# nrf52_pcb_layout.net
KiCad netlist of a schematic drawn in EAGLE
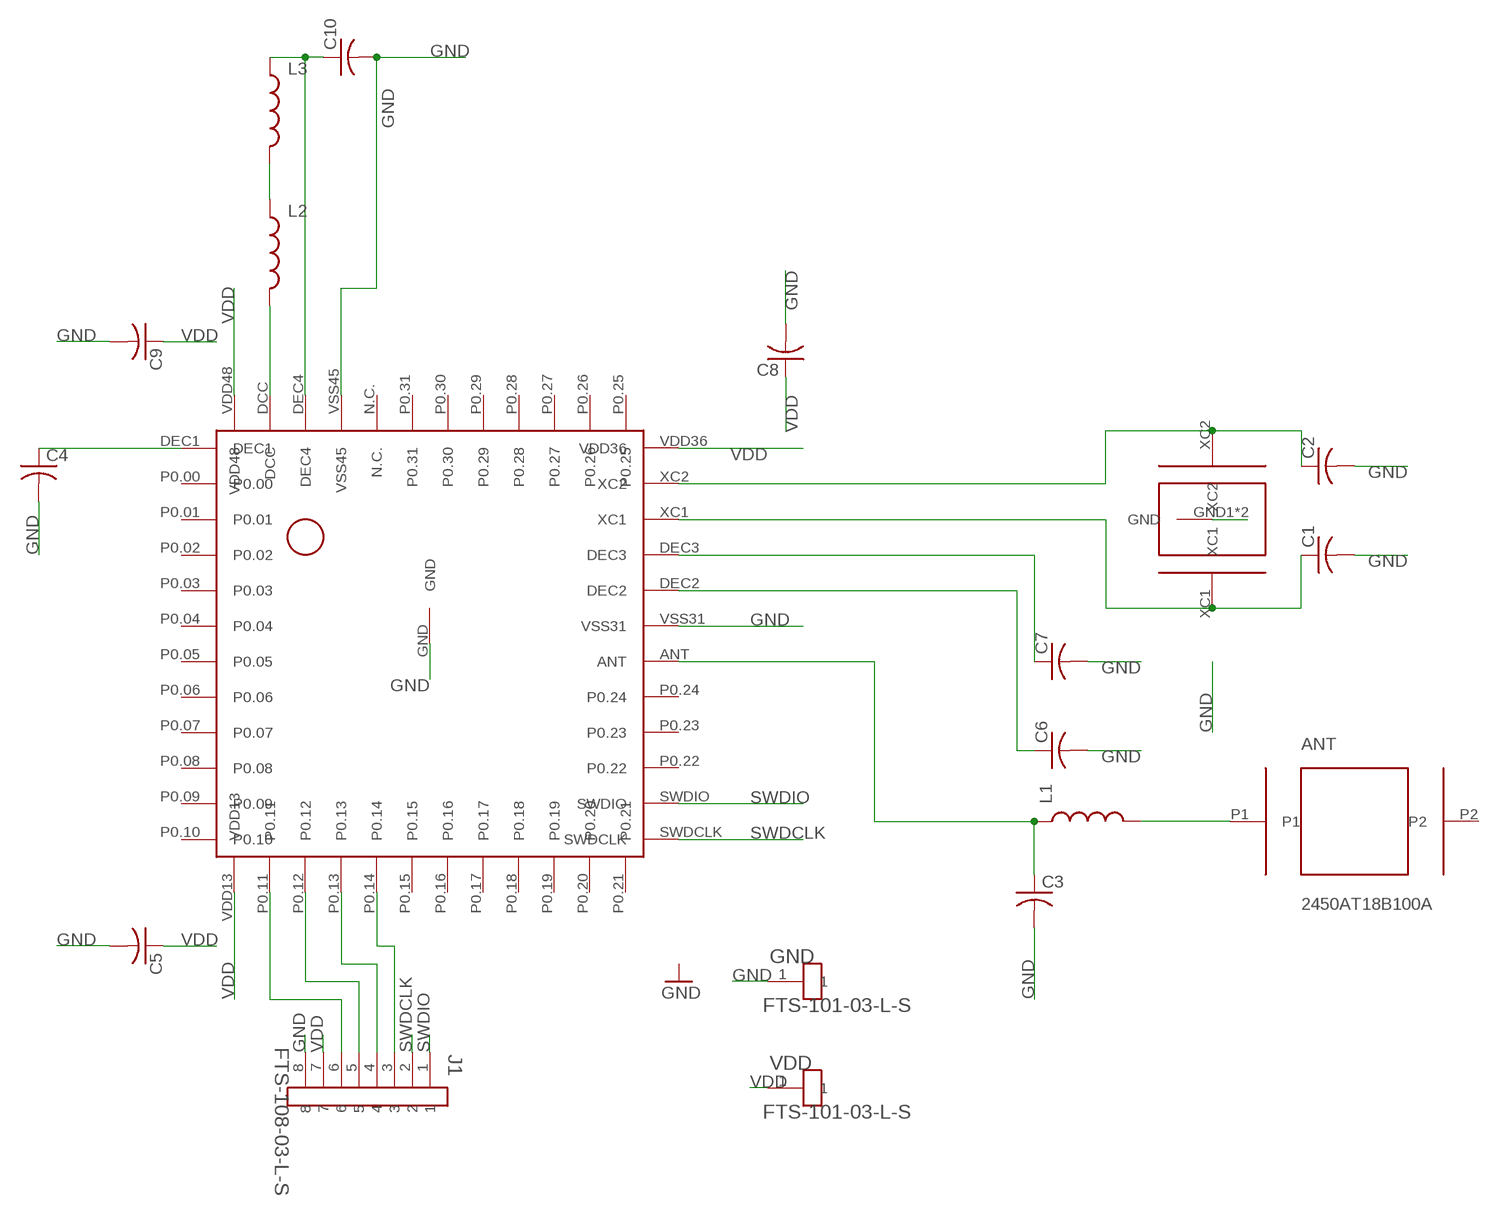
[diagram p0: schematic, sheet 1]

(export (version "E")
  (design (tool "Eeschema 10.0.6"))
  (components
    (comp (ref "ANT")
      (value "2450AT18B100A")
      (footprint "eagle-import:2450AT18B100")
      (libsource (lib "eagle-import") (part "2450AT18B100A"))
    )
    (comp (ref "C1")
      (value "C-USC0402")
      (footprint "eagle-import:C0402")
      (libsource (lib "eagle-import") (part "C-USC0402"))
    )
    (comp (ref "C2")
      (value "C-USC0402")
      (footprint "eagle-import:C0402")
      (libsource (lib "eagle-import") (part "C-USC0402"))
    )
    (comp (ref "C3")
      (value "C-USC0402")
      (footprint "eagle-import:C0402")
      (libsource (lib "eagle-import") (part "C-USC0402"))
    )
    (comp (ref "C4")
      (value "C-USC0402")
      (footprint "eagle-import:C0402")
      (libsource (lib "eagle-import") (part "C-USC0402"))
    )
    (comp (ref "C5")
      (value "C-USC0402")
      (footprint "eagle-import:C0402")
      (libsource (lib "eagle-import") (part "C-USC0402"))
    )
    (comp (ref "C6")
      (value "C-USC0402")
      (footprint "eagle-import:C0402")
      (libsource (lib "eagle-import") (part "C-USC0402"))
    )
    (comp (ref "C7")
      (value "C-USC0402")
      (footprint "eagle-import:C0402")
      (libsource (lib "eagle-import") (part "C-USC0402"))
    )
    (comp (ref "C8")
      (value "C-USC0402")
      (footprint "eagle-import:C0402")
      (libsource (lib "eagle-import") (part "C-USC0402"))
    )
    (comp (ref "C9")
      (value "C-USC0603")
      (footprint "eagle-import:C0603")
      (libsource (lib "eagle-import") (part "C-USC0603"))
    )
    (comp (ref "C10")
      (value "C-USC0603")
      (footprint "eagle-import:C0603")
      (libsource (lib "eagle-import") (part "C-USC0603"))
    )
    (comp (ref "GND")
      (value "FTS-101-03-L-S")
      (footprint "eagle-import:SAMTEC_FTS-101-03-S")
      (libsource (lib "eagle-import") (part "FTS-101-03-L-S"))
    )
    (comp (ref "J1")
      (value "FTS-108-03-L-S")
      (footprint "eagle-import:SAMTEC_FTS-108-03-S")
      (fields (field (name "MPN") "FTS-108-03-L-D"))
      (libsource (lib "eagle-import") (part "FTS-108-03-L-S"))
    )
    (comp (ref "L1")
      (value "INDUCTOR0402")
      (footprint "eagle-import:C0402")
      (libsource (lib "eagle-import") (part "INDUCTOR0402"))
    )
    (comp (ref "L2")
      (value "INDUCTOR0603")
      (footprint "eagle-import:0603")
      (libsource (lib "eagle-import") (part "INDUCTOR0603"))
    )
    (comp (ref "L3")
      (value "INDUCTOR0402")
      (footprint "eagle-import:C0402")
      (libsource (lib "eagle-import") (part "INDUCTOR0402"))
    )
    (comp (ref "NRF52")
      (value "NRF52832-QFN48")
      (footprint "eagle-import:NRF52832-QFN48")
      (libsource (lib "eagle-import") (part "NRF52832-QFN48"))
    )
    (comp (ref "VDD")
      (value "FTS-101-03-L-S")
      (footprint "eagle-import:SAMTEC_FTS-101-03-S")
      (libsource (lib "eagle-import") (part "FTS-101-03-L-S"))
    )
    (comp (ref "X1")
      (value "XTAL-SMD-2016SMD-2016")
      (footprint "eagle-import:XTAL-SMD-2016")
      (libsource (lib "eagle-import") (part "XTAL-SMD-2016SMD-2016"))
    )
  )
  (nets
    (net (code "1") (name "/SWDCLK") (class "Default")
      (node (ref "J1") (pin "2") (pinfunction "2_2") (pintype "passive"))
      (node (ref "NRF52") (pin "SWDCLK") (pinfunction "SWDCLK_SWDCLK") (pintype "bidirectional"))
    )
    (net (code "2") (name "/SWDIO") (class "Default")
      (node (ref "J1") (pin "1") (pinfunction "1_1") (pintype "passive"))
      (node (ref "NRF52") (pin "SWDIO") (pinfunction "SWDIO_SWDIO") (pintype "bidirectional"))
    )
    (net (code "3") (name "/VDD") (class "Default")
      (node (ref "C5") (pin "1") (pinfunction "1_1") (pintype "passive"))
      (node (ref "C8") (pin "1") (pinfunction "1_1") (pintype "passive"))
      (node (ref "C9") (pin "1") (pinfunction "1_1") (pintype "passive"))
      (node (ref "J1") (pin "7") (pinfunction "7_7") (pintype "passive"))
      (node (ref "NRF52") (pin "VDD13") (pinfunction "VDD13_VDD13") (pintype "bidirectional"))
      (node (ref "NRF52") (pin "VDD36") (pinfunction "VDD36_VDD36") (pintype "bidirectional"))
      (node (ref "NRF52") (pin "VDD48") (pinfunction "VDD48_VDD48") (pintype "bidirectional"))
      (node (ref "VDD") (pin "1") (pinfunction "1_1") (pintype "passive"))
    )
    (net (code "4") (name "GND") (class "Default")
      (node (ref "C1") (pin "2") (pinfunction "2_2") (pintype "passive"))
      (node (ref "C10") (pin "2") (pinfunction "2_2") (pintype "passive"))
      (node (ref "C2") (pin "2") (pinfunction "2_2") (pintype "passive"))
      (node (ref "C3") (pin "2") (pinfunction "2_2") (pintype "passive"))
      (node (ref "C4") (pin "2") (pinfunction "2_2") (pintype "passive"))
      (node (ref "C5") (pin "2") (pinfunction "2_2") (pintype "passive"))
      (node (ref "C6") (pin "2") (pinfunction "2_2") (pintype "passive"))
      (node (ref "C7") (pin "2") (pinfunction "2_2") (pintype "passive"))
      (node (ref "C8") (pin "2") (pinfunction "2_2") (pintype "passive"))
      (node (ref "C9") (pin "2") (pinfunction "2_2") (pintype "passive"))
      (node (ref "GND") (pin "1") (pinfunction "1_1") (pintype "passive"))
      (node (ref "J1") (pin "8") (pinfunction "8_8") (pintype "passive"))
      (node (ref "NRF52") (pin "GND") (pinfunction "GND_GND") (pintype "bidirectional"))
      (node (ref "NRF52") (pin "VSS31") (pinfunction "VSS31_VSS31") (pintype "bidirectional"))
      (node (ref "NRF52") (pin "VSS45") (pinfunction "VSS45_VSS45") (pintype "bidirectional"))
      (node (ref "X1") (pin "GND1") (pinfunction "GND_GND1") (pintype "bidirectional"))
      (node (ref "X1") (pin "GND2") (pinfunction "GND_GND2") (pintype "bidirectional"))
    )
    (net (code "5") (name "Net-(ANT-PadP1)") (class "Default")
      (node (ref "ANT") (pin "P1") (pinfunction "P1_P1") (pintype "bidirectional"))
      (node (ref "L1") (pin "2") (pinfunction "2_2") (pintype "passive"))
    )
    (net (code "6") (name "Net-(C1-Pad1)") (class "Default")
      (node (ref "C1") (pin "1") (pinfunction "1_1") (pintype "passive"))
      (node (ref "NRF52") (pin "XC1") (pinfunction "XC1_XC1") (pintype "bidirectional"))
      (node (ref "X1") (pin "XC1") (pinfunction "XC1_XC1") (pintype "bidirectional"))
    )
    (net (code "7") (name "Net-(C2-Pad1)") (class "Default")
      (node (ref "C2") (pin "1") (pinfunction "1_1") (pintype "passive"))
      (node (ref "NRF52") (pin "XC2") (pinfunction "XC2_XC2") (pintype "bidirectional"))
      (node (ref "X1") (pin "XC2") (pinfunction "XC2_XC2") (pintype "bidirectional"))
    )
    (net (code "8") (name "Net-(C3-Pad1)") (class "Default")
      (node (ref "C3") (pin "1") (pinfunction "1_1") (pintype "passive"))
      (node (ref "L1") (pin "1") (pinfunction "1_1") (pintype "passive"))
      (node (ref "NRF52") (pin "ANT") (pinfunction "ANT_ANT") (pintype "bidirectional"))
    )
    (net (code "9") (name "Net-(C4-Pad1)") (class "Default")
      (node (ref "C4") (pin "1") (pinfunction "1_1") (pintype "passive"))
      (node (ref "NRF52") (pin "DEC1") (pinfunction "DEC1_DEC1") (pintype "bidirectional"))
    )
    (net (code "10") (name "Net-(C6-Pad1)") (class "Default")
      (node (ref "C6") (pin "1") (pinfunction "1_1") (pintype "passive"))
      (node (ref "NRF52") (pin "DEC2") (pinfunction "DEC2_DEC2") (pintype "bidirectional"))
    )
    (net (code "11") (name "Net-(C7-Pad1)") (class "Default")
      (node (ref "C7") (pin "1") (pinfunction "1_1") (pintype "passive"))
      (node (ref "NRF52") (pin "DEC3") (pinfunction "DEC3_DEC3") (pintype "bidirectional"))
    )
    (net (code "12") (name "Net-(C10-Pad1)") (class "Default")
      (node (ref "C10") (pin "1") (pinfunction "1_1") (pintype "passive"))
      (node (ref "L3") (pin "1") (pinfunction "1_1") (pintype "passive"))
      (node (ref "NRF52") (pin "DEC4") (pinfunction "DEC4_DEC4") (pintype "bidirectional"))
    )
    (net (code "13") (name "Net-(J1-Pad3)") (class "Default")
      (node (ref "J1") (pin "3") (pinfunction "3_3") (pintype "passive"))
      (node (ref "NRF52") (pin "P0.14") (pinfunction "P0.14_P0.14") (pintype "bidirectional"))
    )
    (net (code "14") (name "Net-(J1-Pad4)") (class "Default")
      (node (ref "J1") (pin "4") (pinfunction "4_4") (pintype "passive"))
      (node (ref "NRF52") (pin "P0.13") (pinfunction "P0.13_P0.13") (pintype "bidirectional"))
    )
    (net (code "15") (name "Net-(J1-Pad5)") (class "Default")
      (node (ref "J1") (pin "5") (pinfunction "5_5") (pintype "passive"))
      (node (ref "NRF52") (pin "P0.12") (pinfunction "P0.12_P0.12") (pintype "bidirectional"))
    )
    (net (code "16") (name "Net-(J1-Pad6)") (class "Default")
      (node (ref "J1") (pin "6") (pinfunction "6_6") (pintype "passive"))
      (node (ref "NRF52") (pin "P0.11") (pinfunction "P0.11_P0.11") (pintype "bidirectional"))
    )
    (net (code "17") (name "Net-(L2-Pad1)") (class "Default")
      (node (ref "L2") (pin "1") (pinfunction "1_1") (pintype "passive"))
      (node (ref "L3") (pin "2") (pinfunction "2_2") (pintype "passive"))
    )
    (net (code "18") (name "Net-(L2-Pad2)") (class "Default")
      (node (ref "L2") (pin "2") (pinfunction "2_2") (pintype "passive"))
      (node (ref "NRF52") (pin "DCC") (pinfunction "DCC_DCC") (pintype "bidirectional"))
    )
    (net (code "19") (name "unconnected-(ANT-PadP2)") (class "Default")
      (node (ref "ANT") (pin "P2") (pinfunction "P2_P2") (pintype "bidirectional"))
    )
    (net (code "20") (name "unconnected-(NRF52-PadN.C.)") (class "Default")
      (node (ref "NRF52") (pin "N.C.") (pinfunction "N.C._N.C.") (pintype "bidirectional"))
    )
    (net (code "21") (name "unconnected-(NRF52-PadP0.00)") (class "Default")
      (node (ref "NRF52") (pin "P0.00") (pinfunction "P0.00_P0.00") (pintype "bidirectional"))
    )
    (net (code "22") (name "unconnected-(NRF52-PadP0.01)") (class "Default")
      (node (ref "NRF52") (pin "P0.01") (pinfunction "P0.01_P0.01") (pintype "bidirectional"))
    )
    (net (code "23") (name "unconnected-(NRF52-PadP0.02)") (class "Default")
      (node (ref "NRF52") (pin "P0.02") (pinfunction "P0.02_P0.02") (pintype "bidirectional"))
    )
    (net (code "24") (name "unconnected-(NRF52-PadP0.03)") (class "Default")
      (node (ref "NRF52") (pin "P0.03") (pinfunction "P0.03_P0.03") (pintype "bidirectional"))
    )
    (net (code "25") (name "unconnected-(NRF52-PadP0.04)") (class "Default")
      (node (ref "NRF52") (pin "P0.04") (pinfunction "P0.04_P0.04") (pintype "bidirectional"))
    )
    (net (code "26") (name "unconnected-(NRF52-PadP0.05)") (class "Default")
      (node (ref "NRF52") (pin "P0.05") (pinfunction "P0.05_P0.05") (pintype "bidirectional"))
    )
    (net (code "27") (name "unconnected-(NRF52-PadP0.06)") (class "Default")
      (node (ref "NRF52") (pin "P0.06") (pinfunction "P0.06_P0.06") (pintype "bidirectional"))
    )
    (net (code "28") (name "unconnected-(NRF52-PadP0.07)") (class "Default")
      (node (ref "NRF52") (pin "P0.07") (pinfunction "P0.07_P0.07") (pintype "bidirectional"))
    )
    (net (code "29") (name "unconnected-(NRF52-PadP0.08)") (class "Default")
      (node (ref "NRF52") (pin "P0.08") (pinfunction "P0.08_P0.08") (pintype "bidirectional"))
    )
    (net (code "30") (name "unconnected-(NRF52-PadP0.09)") (class "Default")
      (node (ref "NRF52") (pin "P0.09") (pinfunction "P0.09_P0.09") (pintype "bidirectional"))
    )
    (net (code "31") (name "unconnected-(NRF52-PadP0.10)") (class "Default")
      (node (ref "NRF52") (pin "P0.10") (pinfunction "P0.10_P0.10") (pintype "bidirectional"))
    )
    (net (code "32") (name "unconnected-(NRF52-PadP0.15)") (class "Default")
      (node (ref "NRF52") (pin "P0.15") (pinfunction "P0.15_P0.15") (pintype "bidirectional"))
    )
    (net (code "33") (name "unconnected-(NRF52-PadP0.16)") (class "Default")
      (node (ref "NRF52") (pin "P0.16") (pinfunction "P0.16_P0.16") (pintype "bidirectional"))
    )
    (net (code "34") (name "unconnected-(NRF52-PadP0.17)") (class "Default")
      (node (ref "NRF52") (pin "P0.17") (pinfunction "P0.17_P0.17") (pintype "bidirectional"))
    )
    (net (code "35") (name "unconnected-(NRF52-PadP0.18)") (class "Default")
      (node (ref "NRF52") (pin "P0.18") (pinfunction "P0.18_P0.18") (pintype "bidirectional"))
    )
    (net (code "36") (name "unconnected-(NRF52-PadP0.19)") (class "Default")
      (node (ref "NRF52") (pin "P0.19") (pinfunction "P0.19_P0.19") (pintype "bidirectional"))
    )
    (net (code "37") (name "unconnected-(NRF52-PadP0.20)") (class "Default")
      (node (ref "NRF52") (pin "P0.20") (pinfunction "P0.20_P0.20") (pintype "bidirectional"))
    )
    (net (code "38") (name "unconnected-(NRF52-PadP0.21)") (class "Default")
      (node (ref "NRF52") (pin "P0.21") (pinfunction "P0.21_P0.21") (pintype "bidirectional"))
    )
    (net (code "39") (name "unconnected-(NRF52-PadP0.22)") (class "Default")
      (node (ref "NRF52") (pin "P0.22") (pinfunction "P0.22_P0.22") (pintype "bidirectional"))
    )
    (net (code "40") (name "unconnected-(NRF52-PadP0.23)") (class "Default")
      (node (ref "NRF52") (pin "P0.23") (pinfunction "P0.23_P0.23") (pintype "bidirectional"))
    )
    (net (code "41") (name "unconnected-(NRF52-PadP0.24)") (class "Default")
      (node (ref "NRF52") (pin "P0.24") (pinfunction "P0.24_P0.24") (pintype "bidirectional"))
    )
    (net (code "42") (name "unconnected-(NRF52-PadP0.25)") (class "Default")
      (node (ref "NRF52") (pin "P0.25") (pinfunction "P0.25_P0.25") (pintype "bidirectional"))
    )
    (net (code "43") (name "unconnected-(NRF52-PadP0.26)") (class "Default")
      (node (ref "NRF52") (pin "P0.26") (pinfunction "P0.26_P0.26") (pintype "bidirectional"))
    )
    (net (code "44") (name "unconnected-(NRF52-PadP0.27)") (class "Default")
      (node (ref "NRF52") (pin "P0.27") (pinfunction "P0.27_P0.27") (pintype "bidirectional"))
    )
    (net (code "45") (name "unconnected-(NRF52-PadP0.28)") (class "Default")
      (node (ref "NRF52") (pin "P0.28") (pinfunction "P0.28_P0.28") (pintype "bidirectional"))
    )
    (net (code "46") (name "unconnected-(NRF52-PadP0.29)") (class "Default")
      (node (ref "NRF52") (pin "P0.29") (pinfunction "P0.29_P0.29") (pintype "bidirectional"))
    )
    (net (code "47") (name "unconnected-(NRF52-PadP0.30)") (class "Default")
      (node (ref "NRF52") (pin "P0.30") (pinfunction "P0.30_P0.30") (pintype "bidirectional"))
    )
    (net (code "48") (name "unconnected-(NRF52-PadP0.31)") (class "Default")
      (node (ref "NRF52") (pin "P0.31") (pinfunction "P0.31_P0.31") (pintype "bidirectional"))
    )
  )
)
